# mmcaudio-analog-in.net
KiCad netlist of a schematic drawn in EAGLE
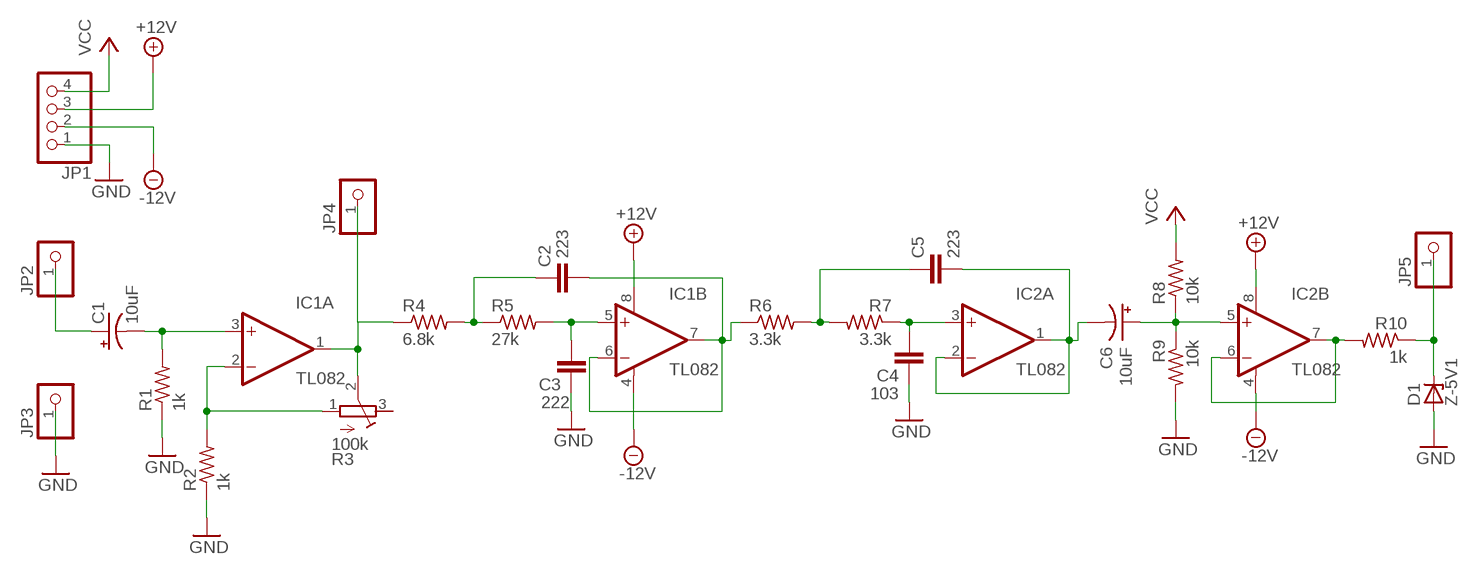
[diagram p0: schematic, sheet 1]

(export (version "E")
  (design (tool "Eeschema 10.0.6"))
  (components
    (comp (ref "C1")
      (value "10uF")
      (footprint "eagle-import:POL-CAP-COMMON")
      (libsource (lib "eagle-import") (part "CPOL-USSANYO_D"))
    )
    (comp (ref "C2")
      (value "223")
      (footprint "eagle-import:C025-060X050")
      (libsource (lib "eagle-import") (part "C-EUCERAMIC-CAP-COMMON"))
    )
    (comp (ref "C3")
      (value "222")
      (footprint "eagle-import:C025-060X050")
      (libsource (lib "eagle-import") (part "C-EUCERAMIC-CAP-COMMON"))
    )
    (comp (ref "C4")
      (value "103")
      (footprint "eagle-import:C025-060X050")
      (libsource (lib "eagle-import") (part "C-EUCERAMIC-CAP-COMMON"))
    )
    (comp (ref "C5")
      (value "223")
      (footprint "eagle-import:C025-060X050")
      (libsource (lib "eagle-import") (part "C-EUCERAMIC-CAP-COMMON"))
    )
    (comp (ref "C6")
      (value "10uF")
      (footprint "eagle-import:POL-CAP-COMMON")
      (libsource (lib "eagle-import") (part "CPOL-USSANYO_D"))
    )
    (comp (ref "D1")
      (value "Z-5V1")
      (footprint "eagle-import:DO35Z7")
      (libsource (lib "eagle-import") (part "Z-5V1"))
    )
    (comp (ref "IC1")
      (value "TL082")
      (footprint "eagle-import:DIP08")
      (libsource (lib "eagle-import") (part "TL082"))
    )
    (comp (ref "IC2")
      (value "TL082")
      (footprint "eagle-import:DIP08")
      (libsource (lib "eagle-import") (part "TL082"))
    )
    (comp (ref "JP1")
      (value "PINHD-1X4")
      (footprint "eagle-import:1X04")
      (libsource (lib "eagle-import") (part "PINHD-1X4"))
    )
    (comp (ref "JP2")
      (value "PINHD-1X1")
      (footprint "eagle-import:1X01")
      (libsource (lib "eagle-import") (part "PINHD-1X1"))
    )
    (comp (ref "JP3")
      (value "PINHD-1X1")
      (footprint "eagle-import:1X01")
      (libsource (lib "eagle-import") (part "PINHD-1X1"))
    )
    (comp (ref "JP4")
      (value "PINHD-1X1")
      (footprint "eagle-import:1X01")
      (libsource (lib "eagle-import") (part "PINHD-1X1"))
    )
    (comp (ref "JP5")
      (value "PINHD-1X1")
      (footprint "eagle-import:1X01")
      (libsource (lib "eagle-import") (part "PINHD-1X1"))
    )
    (comp (ref "R1")
      (value "1k")
      (footprint "eagle-import:R-US-COMMON")
      (libsource (lib "eagle-import") (part "R-US_0207/10"))
    )
    (comp (ref "R2")
      (value "1k")
      (footprint "eagle-import:R-US-COMMON")
      (libsource (lib "eagle-import") (part "R-US_0207/10"))
    )
    (comp (ref "R3")
      (value "100k")
      (footprint "eagle-import:RTRIM-COMMON")
      (libsource (lib "eagle-import") (part "R-TRIMM64W"))
    )
    (comp (ref "R4")
      (value "6.8k")
      (footprint "eagle-import:R-US-COMMON")
      (libsource (lib "eagle-import") (part "R-US_0207/10"))
    )
    (comp (ref "R5")
      (value "27k")
      (footprint "eagle-import:R-US-COMMON")
      (libsource (lib "eagle-import") (part "R-US_0207/10"))
    )
    (comp (ref "R6")
      (value "3.3k")
      (footprint "eagle-import:R-US-COMMON")
      (libsource (lib "eagle-import") (part "R-US_0207/10"))
    )
    (comp (ref "R7")
      (value "3.3k")
      (footprint "eagle-import:R-US-COMMON")
      (libsource (lib "eagle-import") (part "R-US_0207/10"))
    )
    (comp (ref "R8")
      (value "10k")
      (footprint "eagle-import:R-US-COMMON")
      (libsource (lib "eagle-import") (part "R-US_0207/10"))
    )
    (comp (ref "R9")
      (value "10k")
      (footprint "eagle-import:R-US-COMMON")
      (libsource (lib "eagle-import") (part "R-US_0207/10"))
    )
    (comp (ref "R10")
      (value "1k")
      (footprint "eagle-import:R-US-COMMON")
      (libsource (lib "eagle-import") (part "R-US_0207/10"))
    )
  )
  (nets
    (net (code "1") (name "+12V") (class "Default")
      (node (ref "IC1") (pin "8") (pinfunction "V+_8") (pintype "power_in"))
      (node (ref "IC2") (pin "8") (pinfunction "V+_8") (pintype "power_in"))
      (node (ref "JP1") (pin "3") (pinfunction "3_3") (pintype "passive"))
    )
    (net (code "2") (name "-12V") (class "Default")
      (node (ref "IC1") (pin "4") (pinfunction "V-_4") (pintype "power_in"))
      (node (ref "IC2") (pin "4") (pinfunction "V-_4") (pintype "power_in"))
      (node (ref "JP1") (pin "2") (pinfunction "2_2") (pintype "passive"))
    )
    (net (code "3") (name "GND") (class "Default")
      (node (ref "C3") (pin "1") (pinfunction "1_1") (pintype "passive"))
      (node (ref "C4") (pin "1") (pinfunction "1_1") (pintype "passive"))
      (node (ref "D1") (pin "A") (pinfunction "A_A") (pintype "passive"))
      (node (ref "JP1") (pin "1") (pinfunction "1_1") (pintype "passive"))
      (node (ref "JP3") (pin "1") (pinfunction "1_1") (pintype "passive"))
      (node (ref "R1") (pin "1") (pinfunction "1_1") (pintype "passive"))
      (node (ref "R2") (pin "1") (pinfunction "1_1") (pintype "passive"))
      (node (ref "R9") (pin "2") (pinfunction "2_2") (pintype "passive"))
    )
    (net (code "4") (name "Net-(C1-Pad+)") (class "Default")
      (node (ref "C1") (pin "+") (pinfunction "+_+") (pintype "passive"))
      (node (ref "JP2") (pin "1") (pinfunction "1_1") (pintype "passive"))
    )
    (net (code "5") (name "Net-(C2-Pad1)") (class "Default")
      (node (ref "C2") (pin "1") (pinfunction "1_1") (pintype "passive"))
      (node (ref "R4") (pin "2") (pinfunction "2_2") (pintype "passive"))
      (node (ref "R5") (pin "1") (pinfunction "1_1") (pintype "passive"))
    )
    (net (code "6") (name "Net-(C5-Pad1)") (class "Default")
      (node (ref "C5") (pin "1") (pinfunction "1_1") (pintype "passive"))
      (node (ref "R6") (pin "2") (pinfunction "2_2") (pintype "passive"))
      (node (ref "R7") (pin "2") (pinfunction "2_2") (pintype "passive"))
    )
    (net (code "7") (name "Net-(D1-PadC)") (class "Default")
      (node (ref "D1") (pin "C") (pinfunction "C_C") (pintype "passive"))
      (node (ref "JP5") (pin "1") (pinfunction "1_1") (pintype "passive"))
      (node (ref "R10") (pin "1") (pinfunction "1_1") (pintype "passive"))
    )
    (net (code "8") (name "Net-(IC1A-+IN)") (class "Default")
      (node (ref "C1") (pin "-") (pinfunction "-_-") (pintype "passive"))
      (node (ref "IC1") (pin "3") (pinfunction "+IN_3") (pintype "input"))
      (node (ref "R1") (pin "2") (pinfunction "2_2") (pintype "passive"))
    )
    (net (code "9") (name "Net-(IC1A--IN)") (class "Default")
      (node (ref "IC1") (pin "2") (pinfunction "-IN_2") (pintype "input"))
      (node (ref "R2") (pin "2") (pinfunction "2_2") (pintype "passive"))
      (node (ref "R3") (pin "1") (pinfunction "A_1") (pintype "passive"))
    )
    (net (code "10") (name "Net-(IC1A-OUT)") (class "Default")
      (node (ref "IC1") (pin "1") (pinfunction "OUT_1") (pintype "output"))
      (node (ref "JP4") (pin "1") (pinfunction "1_1") (pintype "passive"))
      (node (ref "R3") (pin "2") (pinfunction "S_2") (pintype "passive"))
      (node (ref "R4") (pin "1") (pinfunction "1_1") (pintype "passive"))
    )
    (net (code "11") (name "Net-(IC1B-+IN)") (class "Default")
      (node (ref "C3") (pin "2") (pinfunction "2_2") (pintype "passive"))
      (node (ref "IC1") (pin "5") (pinfunction "+IN_5") (pintype "input"))
      (node (ref "R5") (pin "2") (pinfunction "2_2") (pintype "passive"))
    )
    (net (code "12") (name "Net-(IC1B--IN)") (class "Default")
      (node (ref "C2") (pin "2") (pinfunction "2_2") (pintype "passive"))
      (node (ref "IC1") (pin "6") (pinfunction "-IN_6") (pintype "input"))
      (node (ref "IC1") (pin "7") (pinfunction "OUT_7") (pintype "output"))
      (node (ref "R6") (pin "1") (pinfunction "1_1") (pintype "passive"))
    )
    (net (code "13") (name "Net-(IC2A-+IN)") (class "Default")
      (node (ref "C4") (pin "2") (pinfunction "2_2") (pintype "passive"))
      (node (ref "IC2") (pin "3") (pinfunction "+IN_3") (pintype "input"))
      (node (ref "R7") (pin "1") (pinfunction "1_1") (pintype "passive"))
    )
    (net (code "14") (name "Net-(IC2A--IN)") (class "Default")
      (node (ref "C5") (pin "2") (pinfunction "2_2") (pintype "passive"))
      (node (ref "C6") (pin "-") (pinfunction "-_-") (pintype "passive"))
      (node (ref "IC2") (pin "1") (pinfunction "OUT_1") (pintype "output"))
      (node (ref "IC2") (pin "2") (pinfunction "-IN_2") (pintype "input"))
    )
    (net (code "15") (name "Net-(IC2B-+IN)") (class "Default")
      (node (ref "C6") (pin "+") (pinfunction "+_+") (pintype "passive"))
      (node (ref "IC2") (pin "5") (pinfunction "+IN_5") (pintype "input"))
      (node (ref "R8") (pin "1") (pinfunction "1_1") (pintype "passive"))
      (node (ref "R9") (pin "1") (pinfunction "1_1") (pintype "passive"))
    )
    (net (code "16") (name "Net-(IC2B--IN)") (class "Default")
      (node (ref "IC2") (pin "6") (pinfunction "-IN_6") (pintype "input"))
      (node (ref "IC2") (pin "7") (pinfunction "OUT_7") (pintype "output"))
      (node (ref "R10") (pin "2") (pinfunction "2_2") (pintype "passive"))
    )
    (net (code "17") (name "VCC") (class "Default")
      (node (ref "JP1") (pin "4") (pinfunction "4_4") (pintype "passive"))
      (node (ref "R8") (pin "2") (pinfunction "2_2") (pintype "passive"))
    )
    (net (code "18") (name "unconnected-(R3-E-Pad3)") (class "Default")
      (node (ref "R3") (pin "3") (pinfunction "E_3") (pintype "passive"))
    )
  )
)
